# -.net
KiCad netlist of a schematic drawn in Altium Designer
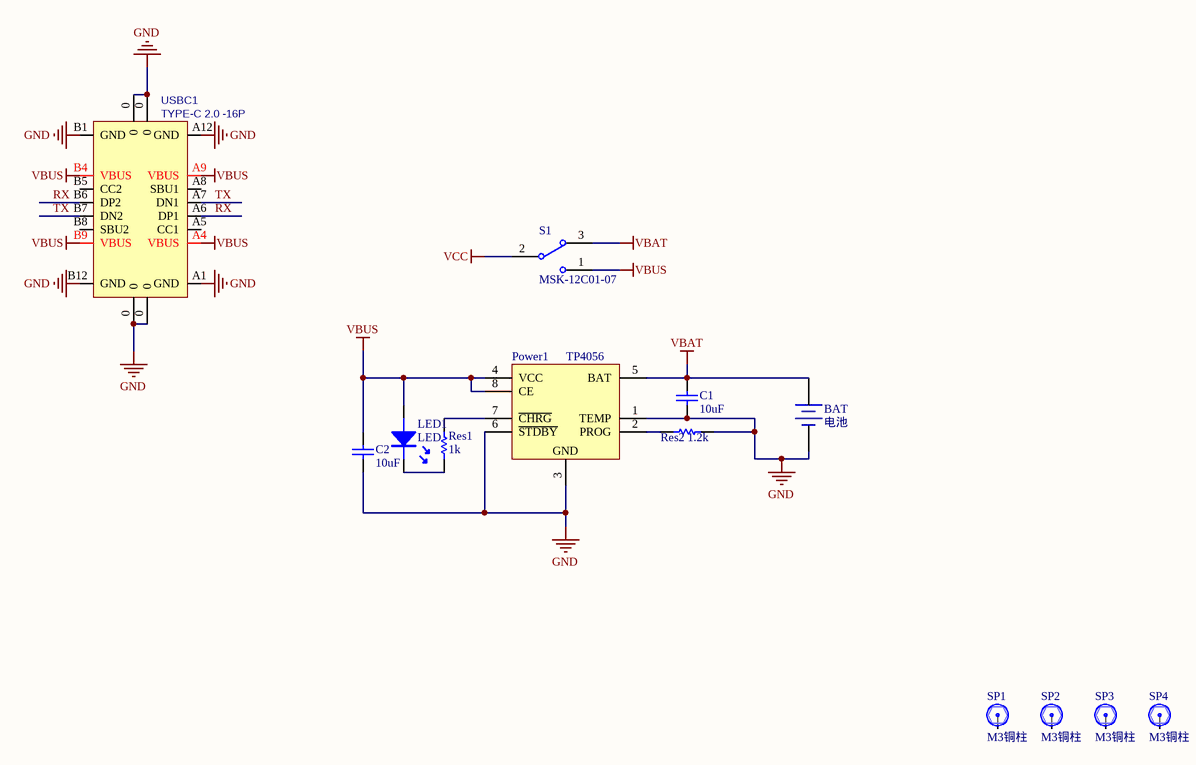
[diagram p0: 底板-供电.SchDoc]

(export (version "E")
  (design (tool "Eeschema 10.0.6"))
  (components
    (comp (ref "BAT")
      (value "电池")
      (footprint "CR1220_A")
      (description "微型电池")
      (libsource (lib "0.7 - 常用按键-开关-蜂鸣器-电池-测试点") (part "CR-3V"))
    )
    (comp (ref "C1")
      (value "10uF")
      (footprint "C0805_L")
      (description "Capacitor")
      (fields (field (name "PUBLISHER") "Altium Limited"))
      (libsource (lib "Miscellaneous Devices") (part "Cap"))
    )
    (comp (ref "C2")
      (value "10uF")
      (footprint "C0805_L")
      (description "Capacitor")
      (fields (field (name "PUBLISHER") "Altium Limited"))
      (libsource (lib "Miscellaneous Devices") (part "Cap"))
    )
    (comp (ref "LED1") (value "LED") (footprint "LED-0603B") (libsource (lib "LED") (part "LED")))
    (comp (ref "Power1") (value "TP4056") (footprint "SOP8") (libsource (lib "电源芯片") (part "TP4056")))
    (comp (ref "Res1") (value "1k") (footprint "0805R") (libsource (lib "电阻") (part "RES")))
    (comp (ref "Res2") (value "1.2k") (footprint "0805R") (libsource (lib "电阻") (part "RES")))
    (comp (ref "S1")
      (value "MSK-12C01-07")
      (footprint "MSK-12C01-07")
      (libsource (lib "电源开关") (part "MSK-12C01-07"))
    )
    (comp (ref "SP1")
      (value "M3铜柱")
      (footprint "M3x4_L")
      (description "铜柱")
      (libsource (lib "0.7 - 常用按键-开关-蜂鸣器-电池-测试点") (part "铜柱小焊盘"))
    )
    (comp (ref "SP2")
      (value "M3铜柱")
      (footprint "M3x4_L")
      (description "铜柱")
      (libsource (lib "0.7 - 常用按键-开关-蜂鸣器-电池-测试点") (part "铜柱小焊盘"))
    )
    (comp (ref "SP3")
      (value "M3铜柱")
      (footprint "M3x4_L")
      (description "铜柱")
      (libsource (lib "0.7 - 常用按键-开关-蜂鸣器-电池-测试点") (part "铜柱小焊盘"))
    )
    (comp (ref "SP4")
      (value "M3铜柱")
      (footprint "M3x4_L")
      (description "铜柱")
      (libsource (lib "0.7 - 常用按键-开关-蜂鸣器-电池-测试点") (part "铜柱小焊盘"))
    )
    (comp (ref "USBC1")
      (value "TYPE-C 2.0 -16P")
      (footprint "USB-C-SMD_16P")
      (description "USB2.0 Type-C 16Pin  母座")
      (libsource (lib "0.8 - 以太网-音频-Type-C USB插座") (part "USB2.0_Type-C_16Pin"))
    )
  )
  (nets
    (net (code "1") (name "/RX") (class "Default")
      (node (ref "USBC1") (pin "A6") (pinfunction "DP1_A6") (pintype "passive"))
      (node (ref "USBC1") (pin "B6") (pinfunction "DP2_B6") (pintype "passive"))
    )
    (net (code "2") (name "/TX") (class "Default")
      (node (ref "USBC1") (pin "A7") (pinfunction "DN1_A7") (pintype "passive"))
      (node (ref "USBC1") (pin "B7") (pinfunction "DN2_B7") (pintype "passive"))
    )
    (net (code "3") (name "GND") (class "Default")
      (node (ref "BAT") (pin "2") (pinfunction "DC-_2") (pintype "passive"))
      (node (ref "C1") (pin "1") (pinfunction "1_1") (pintype "passive"))
      (node (ref "C2") (pin "1") (pinfunction "1_1") (pintype "passive"))
      (node (ref "Power1") (pin "1") (pinfunction "TEMP_1") (pintype "passive"))
      (node (ref "Power1") (pin "3") (pinfunction "GND_3") (pintype "passive"))
      (node (ref "Power1") (pin "6") (pinfunction "~{STDBY}_6") (pintype "passive"))
      (node (ref "Res2") (pin "1") (pinfunction "1_1") (pintype "passive"))
      (node (ref "USBC1") (pin "0") (pinfunction "0_0") (pintype "passive"))
      (node (ref "USBC1") (pin "A1") (pinfunction "GND_A1") (pintype "passive"))
      (node (ref "USBC1") (pin "A12") (pinfunction "GND_A12") (pintype "passive"))
      (node (ref "USBC1") (pin "B1") (pinfunction "GND_B1") (pintype "passive"))
      (node (ref "USBC1") (pin "B12") (pinfunction "GND_B12") (pintype "passive"))
    )
    (net (code "4") (name "Net-(LED1-PadK)") (class "Default")
      (node (ref "LED1") (pin "K") (pinfunction "K_K") (pintype "passive"))
      (node (ref "Res1") (pin "2") (pinfunction "2_2") (pintype "passive"))
    )
    (net (code "5") (name "Net-(Power1-PROG)") (class "Default")
      (node (ref "Power1") (pin "2") (pinfunction "PROG_2") (pintype "passive"))
      (node (ref "Res2") (pin "2") (pinfunction "2_2") (pintype "passive"))
    )
    (net (code "6") (name "Net-(Power1-~{CHRG})") (class "Default")
      (node (ref "Power1") (pin "7") (pinfunction "~{CHRG}_7") (pintype "passive"))
      (node (ref "Res1") (pin "1") (pinfunction "1_1") (pintype "passive"))
    )
    (net (code "7") (name "VBAT") (class "Default")
      (node (ref "BAT") (pin "1") (pinfunction "DC+_1") (pintype "passive"))
      (node (ref "C1") (pin "2") (pinfunction "2_2") (pintype "passive"))
      (node (ref "Power1") (pin "5") (pinfunction "BAT_5") (pintype "passive"))
      (node (ref "S1") (pin "3") (pinfunction "3_3") (pintype "passive"))
    )
    (net (code "8") (name "VBUS") (class "Default")
      (node (ref "C2") (pin "2") (pinfunction "2_2") (pintype "passive"))
      (node (ref "LED1") (pin "A") (pinfunction "A_A") (pintype "passive"))
      (node (ref "Power1") (pin "4") (pinfunction "VCC_4") (pintype "passive"))
      (node (ref "Power1") (pin "8") (pinfunction "CE_8") (pintype "passive"))
      (node (ref "S1") (pin "1") (pinfunction "1_1") (pintype "passive"))
      (node (ref "USBC1") (pin "A4") (pinfunction "VBUS_A4") (pintype "passive"))
      (node (ref "USBC1") (pin "A9") (pinfunction "VBUS_A9") (pintype "passive"))
      (node (ref "USBC1") (pin "B4") (pinfunction "VBUS_B4") (pintype "passive"))
      (node (ref "USBC1") (pin "B9") (pinfunction "VBUS_B9") (pintype "passive"))
    )
    (net (code "9") (name "VCC") (class "Default")
      (node (ref "S1") (pin "2") (pinfunction "2_2") (pintype "passive"))
    )
    (net (code "10") (name "unconnected-(SP1-Pad1)") (class "Default")
      (node (ref "SP1") (pin "1") (pinfunction "1_1") (pintype "passive"))
    )
    (net (code "11") (name "unconnected-(SP2-Pad1)") (class "Default")
      (node (ref "SP2") (pin "1") (pinfunction "1_1") (pintype "passive"))
    )
    (net (code "12") (name "unconnected-(SP3-Pad1)") (class "Default")
      (node (ref "SP3") (pin "1") (pinfunction "1_1") (pintype "passive"))
    )
    (net (code "13") (name "unconnected-(SP4-Pad1)") (class "Default")
      (node (ref "SP4") (pin "1") (pinfunction "1_1") (pintype "passive"))
    )
    (net (code "14") (name "unconnected-(USBC1-CC1-PadA5)") (class "Default")
      (node (ref "USBC1") (pin "A5") (pinfunction "CC1_A5") (pintype "passive"))
    )
    (net (code "15") (name "unconnected-(USBC1-CC2-PadB5)") (class "Default")
      (node (ref "USBC1") (pin "B5") (pinfunction "CC2_B5") (pintype "passive"))
    )
    (net (code "16") (name "unconnected-(USBC1-SBU1-PadA8)") (class "Default")
      (node (ref "USBC1") (pin "A8") (pinfunction "SBU1_A8") (pintype "passive"))
    )
    (net (code "17") (name "unconnected-(USBC1-SBU2-PadB8)") (class "Default")
      (node (ref "USBC1") (pin "B8") (pinfunction "SBU2_B8") (pintype "passive"))
    )
  )
)
